# daughter_board.net
KiCad netlist of a schematic drawn in EAGLE
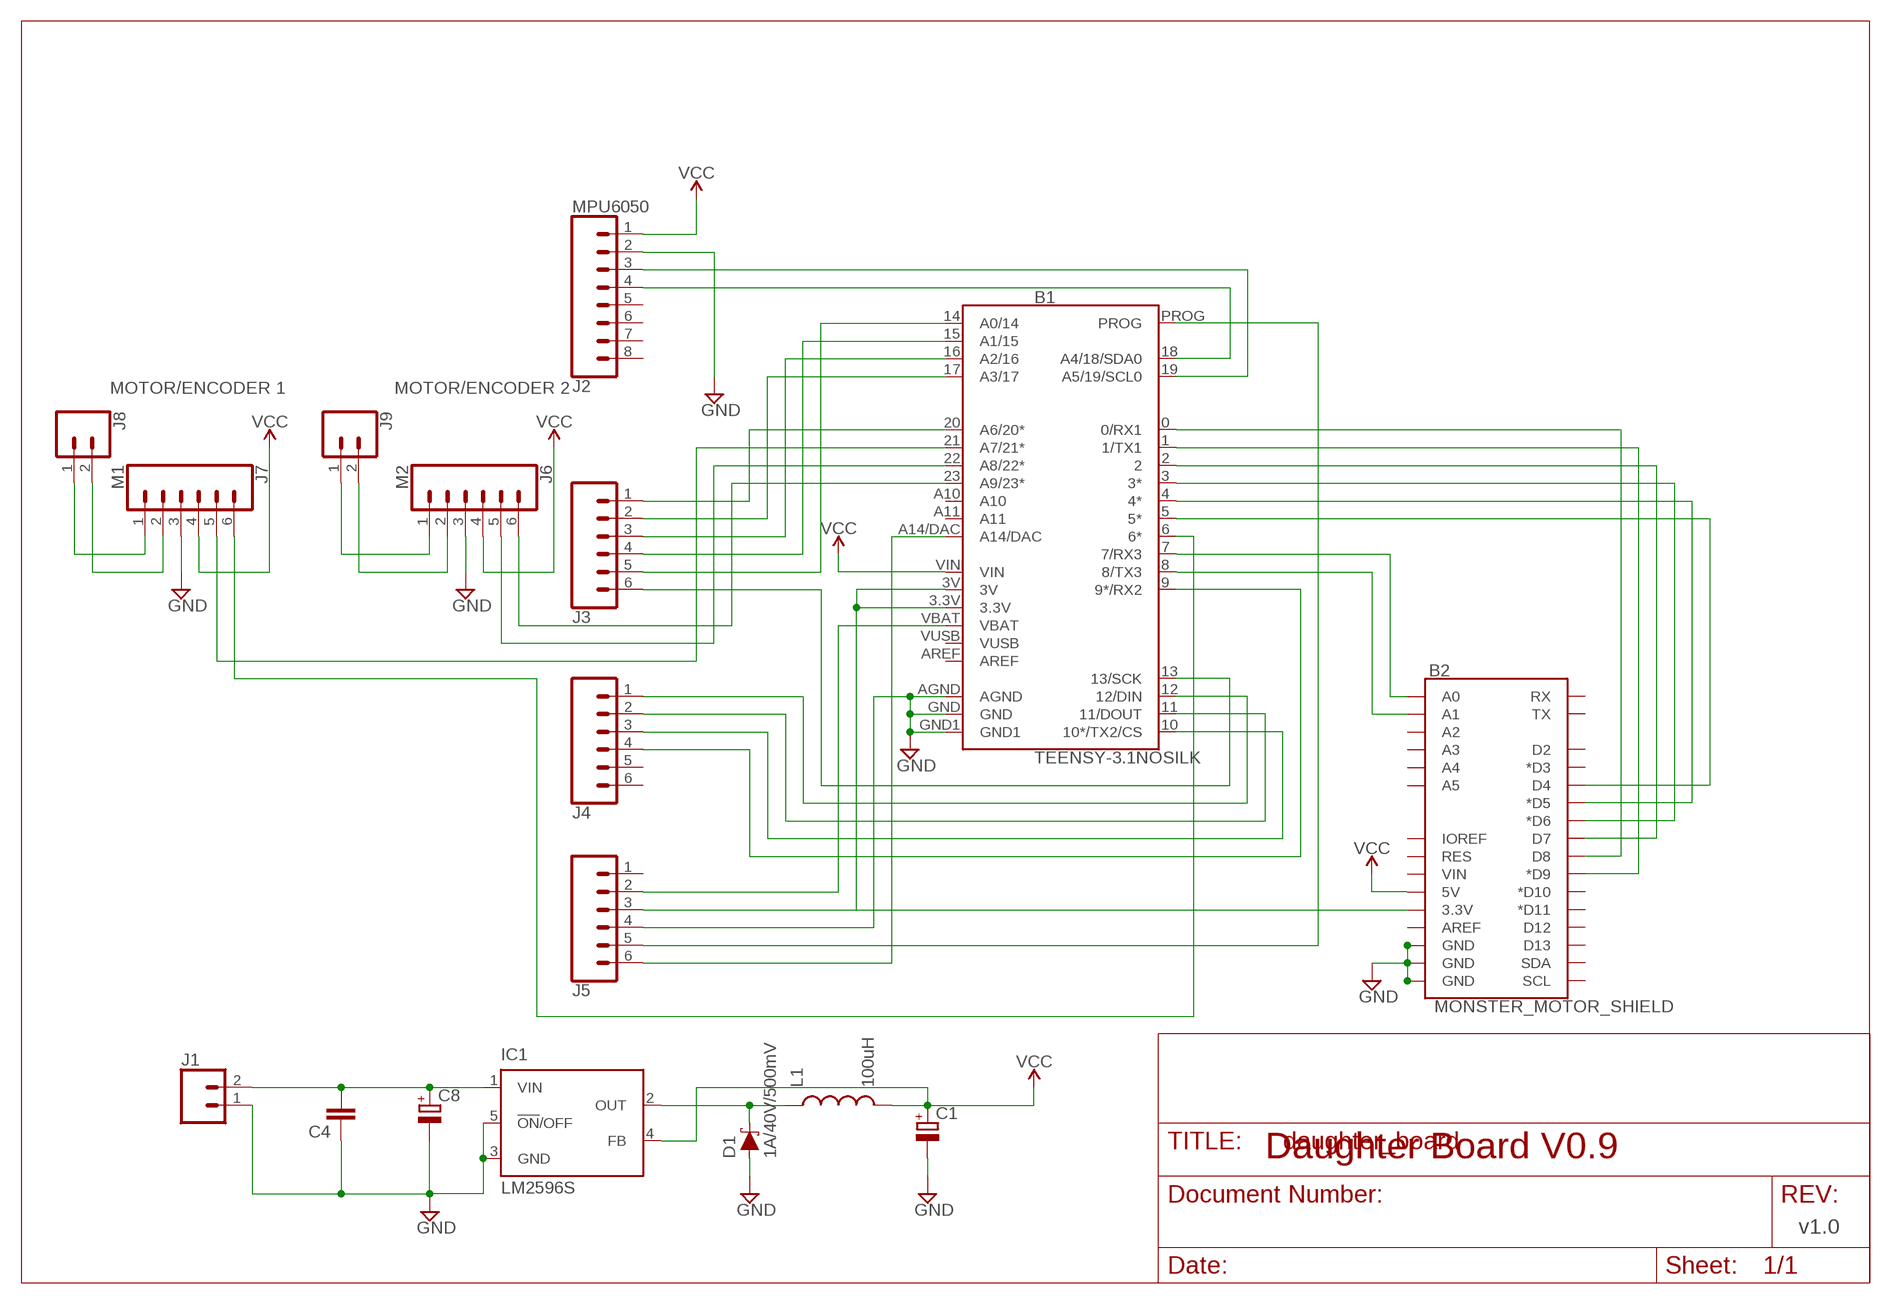
[diagram p0: schematic, sheet 1]

(export (version "E")
  (design (tool "Eeschema 10.0.6"))
  (components
    (comp (ref "B1")
      (value "TEENSY-3.1NOSILK")
      (footprint "eagle-import:TEENSY-3.1_NOSILK")
      (libsource (lib "eagle-import") (part "TEENSY-3.1NOSILK"))
    )
    (comp (ref "B2")
      (value "MONSTER_MOTOR_SHIELD")
      (footprint "eagle-import:UNO_R3_SHIELD_NOLABELS")
      (libsource (lib "eagle-import") (part "ARDUINO_UNO_R3_SHIELDNOLABELS"))
    )
    (comp (ref "C1")
      (value "CPOL-EU150CLZ-0810")
      (footprint "eagle-import:150CLZ-0810")
      (libsource (lib "eagle-import") (part "CPOL-EU150CLZ-0810"))
    )
    (comp (ref "C4")
      (value "C-EUC0805")
      (footprint "eagle-import:C0805")
      (libsource (lib "eagle-import") (part "C-EUC0805"))
    )
    (comp (ref "C8")
      (value "CPOL-EU150CLZ-0810")
      (footprint "eagle-import:150CLZ-0810")
      (libsource (lib "eagle-import") (part "CPOL-EU150CLZ-0810"))
    )
    (comp (ref "D1")
      (value "1A/40V/500mV")
      (footprint "eagle-import:SMA-DIODE")
      (libsource (lib "eagle-import") (part "DIODE-SCHOTTKY-SS14"))
    )
    (comp (ref "IC1")
      (value "LM2596S")
      (footprint "eagle-import:TO263-5")
      (fields (field (name "MF") "NATIONAL SEMICONDUCTOR") (field (name "MPN") "LM2596S-ADJ/NOPB"))
      (libsource (lib "eagle-import") (part "LM2596S"))
    )
    (comp (ref "J1")
      (value "CONN_023.5MM-NO_SILK")
      (footprint "eagle-import:SCREWTERMINAL-3.5MM-2-NS")
      (fields (field (name "PROD_ID") "CONN-08399"))
      (libsource (lib "eagle-import") (part "CONN_023.5MM-NO_SILK"))
    )
    (comp (ref "J2")
      (value "MPU6050")
      (footprint "eagle-import:1X08_NO_SILK")
      (libsource (lib "eagle-import") (part "CONN_08NO_SILK_FEMALE_PTH"))
    )
    (comp (ref "J3")
      (value "CONN_06NO_SILK_FEMALE_PTH")
      (footprint "eagle-import:1X06_NO_SILK")
      (libsource (lib "eagle-import") (part "CONN_06NO_SILK_FEMALE_PTH"))
    )
    (comp (ref "J4")
      (value "CONN_06NO_SILK_FEMALE_PTH")
      (footprint "eagle-import:1X06_NO_SILK")
      (libsource (lib "eagle-import") (part "CONN_06NO_SILK_FEMALE_PTH"))
    )
    (comp (ref "J5")
      (value "CONN_06NO_SILK_FEMALE_PTH")
      (footprint "eagle-import:1X06_NO_SILK")
      (libsource (lib "eagle-import") (part "CONN_06NO_SILK_FEMALE_PTH"))
    )
    (comp (ref "J6")
      (value "M2")
      (footprint "eagle-import:1X06_NO_SILK")
      (libsource (lib "eagle-import") (part "CONN_06NO_SILK_FEMALE_PTH"))
    )
    (comp (ref "J7")
      (value "M1")
      (footprint "eagle-import:1X06_NO_SILK")
      (libsource (lib "eagle-import") (part "CONN_06NO_SILK_FEMALE_PTH"))
    )
    (comp (ref "J8")
      (value "CONN_023.5MM-NO_SILK")
      (footprint "eagle-import:SCREWTERMINAL-3.5MM-2-NS")
      (libsource (lib "eagle-import") (part "CONN_023.5MM-NO_SILK"))
    )
    (comp (ref "J9")
      (value "CONN_023.5MM-NO_SILK")
      (footprint "eagle-import:SCREWTERMINAL-3.5MM-2-NS")
      (libsource (lib "eagle-import") (part "CONN_023.5MM-NO_SILK"))
    )
    (comp (ref "L1")
      (value "100uH")
      (footprint "eagle-import:CDRH125")
      (libsource (lib "eagle-import") (part "INDUCTORPWR"))
    )
  )
  (nets
    (net (code "1") (name "/VUSB") (class "Default")
      (node (ref "B1") (pin "VUSB") (pinfunction "VUSB_VUSB") (pintype "power_in"))
    )
    (net (code "2") (name "GND") (class "Default")
      (node (ref "B1") (pin "AGND") (pinfunction "AGND_AGND") (pintype "power_in"))
      (node (ref "B1") (pin "GND") (pinfunction "GND_GND") (pintype "power_in"))
      (node (ref "B1") (pin "GND1") (pinfunction "GND1_GND1") (pintype "power_in"))
      (node (ref "B2") (pin "GND@0") (pinfunction "GND_GND@0") (pintype "bidirectional"))
      (node (ref "B2") (pin "GND@1") (pinfunction "GND_GND@1") (pintype "bidirectional"))
      (node (ref "B2") (pin "GND@2") (pinfunction "GND_GND@2") (pintype "bidirectional"))
      (node (ref "C1") (pin "-") (pinfunction "-_-") (pintype "passive"))
      (node (ref "C4") (pin "1") (pinfunction "1_1") (pintype "passive"))
      (node (ref "C8") (pin "-") (pinfunction "-_-") (pintype "passive"))
      (node (ref "D1") (pin "A") (pinfunction "A_A") (pintype "passive"))
      (node (ref "IC1") (pin "3") (pinfunction "GND_3") (pintype "power_in"))
      (node (ref "IC1") (pin "5") (pinfunction "~{ON}/OFF_5") (pintype "input"))
      (node (ref "J1") (pin "1") (pinfunction "1_1") (pintype "passive"))
      (node (ref "J2") (pin "2") (pinfunction "2_2") (pintype "passive"))
      (node (ref "J5") (pin "4") (pinfunction "4_4") (pintype "passive"))
      (node (ref "J6") (pin "3") (pinfunction "3_3") (pintype "passive"))
      (node (ref "J7") (pin "3") (pinfunction "3_3") (pintype "passive"))
    )
    (net (code "3") (name "Net-(B1-0{slash}RX1)") (class "Default")
      (node (ref "B1") (pin "0") (pinfunction "0/RX1_0") (pintype "bidirectional"))
      (node (ref "B2") (pin "D8") (pinfunction "D8_D8") (pintype "bidirectional"))
    )
    (net (code "4") (name "Net-(B1-1{slash}TX1)") (class "Default")
      (node (ref "B1") (pin "1") (pinfunction "1/TX1_1") (pintype "bidirectional"))
      (node (ref "B2") (pin "D9") (pinfunction "*D9_D9") (pintype "bidirectional"))
    )
    (net (code "5") (name "Net-(B1-3*)") (class "Default")
      (node (ref "B1") (pin "3") (pinfunction "3*_3") (pintype "bidirectional"))
      (node (ref "B2") (pin "D6") (pinfunction "*D6_D6") (pintype "bidirectional"))
    )
    (net (code "6") (name "Net-(B1-4*)") (class "Default")
      (node (ref "B1") (pin "4") (pinfunction "4*_4") (pintype "bidirectional"))
      (node (ref "B2") (pin "D5") (pinfunction "*D5_D5") (pintype "bidirectional"))
    )
    (net (code "7") (name "Net-(B1-5*)") (class "Default")
      (node (ref "B1") (pin "5") (pinfunction "5*_5") (pintype "bidirectional"))
      (node (ref "B2") (pin "D4") (pinfunction "D4_D4") (pintype "bidirectional"))
    )
    (net (code "8") (name "Net-(B1-6*)") (class "Default")
      (node (ref "B1") (pin "6") (pinfunction "6*_6") (pintype "bidirectional"))
      (node (ref "J7") (pin "6") (pinfunction "6_6") (pintype "passive"))
    )
    (net (code "9") (name "Net-(B1-7{slash}RX3)") (class "Default")
      (node (ref "B1") (pin "7") (pinfunction "7/RX3_7") (pintype "bidirectional"))
      (node (ref "B2") (pin "A0") (pinfunction "A0_A0") (pintype "bidirectional"))
    )
    (net (code "10") (name "Net-(B1-8{slash}TX3)") (class "Default")
      (node (ref "B1") (pin "8") (pinfunction "8/TX3_8") (pintype "bidirectional"))
      (node (ref "B2") (pin "A1") (pinfunction "A1_A1") (pintype "bidirectional"))
    )
    (net (code "11") (name "Net-(B1-9*{slash}RX2)") (class "Default")
      (node (ref "B1") (pin "9") (pinfunction "9*/RX2_9") (pintype "bidirectional"))
      (node (ref "J4") (pin "4") (pinfunction "4_4") (pintype "passive"))
    )
    (net (code "12") (name "Net-(B1-10*{slash}TX2{slash}CS)") (class "Default")
      (node (ref "B1") (pin "10") (pinfunction "10*/TX2/CS_10") (pintype "bidirectional"))
      (node (ref "J4") (pin "3") (pinfunction "3_3") (pintype "passive"))
    )
    (net (code "13") (name "Net-(B1-11{slash}DOUT)") (class "Default")
      (node (ref "B1") (pin "11") (pinfunction "11/DOUT_11") (pintype "bidirectional"))
      (node (ref "J4") (pin "2") (pinfunction "2_2") (pintype "passive"))
    )
    (net (code "14") (name "Net-(B1-12{slash}DIN)") (class "Default")
      (node (ref "B1") (pin "12") (pinfunction "12/DIN_12") (pintype "bidirectional"))
      (node (ref "J4") (pin "1") (pinfunction "1_1") (pintype "passive"))
    )
    (net (code "15") (name "Net-(B1-13{slash}SCK)") (class "Default")
      (node (ref "B1") (pin "13") (pinfunction "13/SCK_13") (pintype "bidirectional"))
      (node (ref "J3") (pin "6") (pinfunction "6_6") (pintype "passive"))
    )
    (net (code "16") (name "Net-(B1-A0{slash}14)") (class "Default")
      (node (ref "B1") (pin "14") (pinfunction "A0/14_14") (pintype "bidirectional"))
      (node (ref "J3") (pin "5") (pinfunction "5_5") (pintype "passive"))
    )
    (net (code "17") (name "Net-(B1-A1{slash}15)") (class "Default")
      (node (ref "B1") (pin "15") (pinfunction "A1/15_15") (pintype "bidirectional"))
      (node (ref "J3") (pin "4") (pinfunction "4_4") (pintype "passive"))
    )
    (net (code "18") (name "Net-(B1-A2{slash}16)") (class "Default")
      (node (ref "B1") (pin "16") (pinfunction "A2/16_16") (pintype "bidirectional"))
      (node (ref "J3") (pin "3") (pinfunction "3_3") (pintype "passive"))
    )
    (net (code "19") (name "Net-(B1-A3{slash}17)") (class "Default")
      (node (ref "B1") (pin "17") (pinfunction "A3/17_17") (pintype "bidirectional"))
      (node (ref "J3") (pin "2") (pinfunction "2_2") (pintype "passive"))
    )
    (net (code "20") (name "Net-(B1-A4{slash}18{slash}SDA0)") (class "Default")
      (node (ref "B1") (pin "18") (pinfunction "A4/18/SDA0_18") (pintype "bidirectional"))
      (node (ref "J2") (pin "4") (pinfunction "4_4") (pintype "passive"))
    )
    (net (code "21") (name "Net-(B1-A5{slash}19{slash}SCL0)") (class "Default")
      (node (ref "B1") (pin "19") (pinfunction "A5/19/SCL0_19") (pintype "bidirectional"))
      (node (ref "J2") (pin "3") (pinfunction "3_3") (pintype "passive"))
    )
    (net (code "22") (name "Net-(B1-A6{slash}20*)") (class "Default")
      (node (ref "B1") (pin "20") (pinfunction "A6/20*_20") (pintype "bidirectional"))
      (node (ref "J3") (pin "1") (pinfunction "1_1") (pintype "passive"))
    )
    (net (code "23") (name "Net-(B1-A7{slash}21*)") (class "Default")
      (node (ref "B1") (pin "21") (pinfunction "A7/21*_21") (pintype "bidirectional"))
      (node (ref "J7") (pin "5") (pinfunction "5_5") (pintype "passive"))
    )
    (net (code "24") (name "Net-(B1-A8{slash}22*)") (class "Default")
      (node (ref "B1") (pin "22") (pinfunction "A8/22*_22") (pintype "bidirectional"))
      (node (ref "J6") (pin "5") (pinfunction "5_5") (pintype "passive"))
    )
    (net (code "25") (name "Net-(B1-A9{slash}23*)") (class "Default")
      (node (ref "B1") (pin "23") (pinfunction "A9/23*_23") (pintype "bidirectional"))
      (node (ref "J6") (pin "6") (pinfunction "6_6") (pintype "passive"))
    )
    (net (code "26") (name "Net-(B1-Pad2)") (class "Default")
      (node (ref "B1") (pin "2") (pinfunction "2_2") (pintype "bidirectional"))
      (node (ref "B2") (pin "D7") (pinfunction "D7_D7") (pintype "bidirectional"))
    )
    (net (code "27") (name "Net-(B1-Pad3.3V)") (class "Default")
      (node (ref "B1") (pin "3.3V") (pinfunction "3.3V_3.3V") (pintype "power_in"))
      (node (ref "B1") (pin "3V") (pinfunction "3V_3V") (pintype "power_in"))
      (node (ref "B2") (pin "3.3V") (pinfunction "3.3V_3.3V") (pintype "bidirectional"))
      (node (ref "J5") (pin "3") (pinfunction "3_3") (pintype "passive"))
    )
    (net (code "28") (name "Net-(B1-PadA14{slash}DAC)") (class "Default")
      (node (ref "B1") (pin "A14/DAC") (pinfunction "A14/DAC_A14/DAC") (pintype "bidirectional"))
      (node (ref "J5") (pin "6") (pinfunction "6_6") (pintype "passive"))
    )
    (net (code "29") (name "Net-(B1-PadPROG)") (class "Default")
      (node (ref "B1") (pin "PROG") (pinfunction "PROG_PROG") (pintype "bidirectional"))
      (node (ref "J5") (pin "5") (pinfunction "5_5") (pintype "passive"))
    )
    (net (code "30") (name "Net-(B1-PadVBAT)") (class "Default")
      (node (ref "B1") (pin "VBAT") (pinfunction "VBAT_VBAT") (pintype "power_in"))
      (node (ref "J5") (pin "2") (pinfunction "2_2") (pintype "passive"))
    )
    (net (code "31") (name "Net-(IC1-OUT)") (class "Default")
      (node (ref "D1") (pin "C") (pinfunction "C_C") (pintype "passive"))
      (node (ref "IC1") (pin "2") (pinfunction "OUT_2") (pintype "output"))
      (node (ref "L1") (pin "1") (pinfunction "1_1") (pintype "passive"))
    )
    (net (code "32") (name "Net-(IC1-VIN)") (class "Default")
      (node (ref "C4") (pin "2") (pinfunction "2_2") (pintype "passive"))
      (node (ref "C8") (pin "+") (pinfunction "+_+") (pintype "passive"))
      (node (ref "IC1") (pin "1") (pinfunction "VIN_1") (pintype "input"))
      (node (ref "J1") (pin "2") (pinfunction "2_2") (pintype "passive"))
    )
    (net (code "33") (name "Net-(J6-Pad1)") (class "Default")
      (node (ref "J6") (pin "1") (pinfunction "1_1") (pintype "passive"))
      (node (ref "J9") (pin "1") (pinfunction "1_1") (pintype "passive"))
    )
    (net (code "34") (name "Net-(J6-Pad2)") (class "Default")
      (node (ref "J6") (pin "2") (pinfunction "2_2") (pintype "passive"))
      (node (ref "J9") (pin "2") (pinfunction "2_2") (pintype "passive"))
    )
    (net (code "35") (name "Net-(J7-Pad1)") (class "Default")
      (node (ref "J7") (pin "1") (pinfunction "1_1") (pintype "passive"))
      (node (ref "J8") (pin "1") (pinfunction "1_1") (pintype "passive"))
    )
    (net (code "36") (name "Net-(J7-Pad2)") (class "Default")
      (node (ref "J7") (pin "2") (pinfunction "2_2") (pintype "passive"))
      (node (ref "J8") (pin "2") (pinfunction "2_2") (pintype "passive"))
    )
    (net (code "37") (name "VCC") (class "Default")
      (node (ref "B1") (pin "VIN") (pinfunction "VIN_VIN") (pintype "power_in"))
      (node (ref "B2") (pin "5V") (pinfunction "5V_5V") (pintype "bidirectional"))
      (node (ref "C1") (pin "+") (pinfunction "+_+") (pintype "passive"))
      (node (ref "IC1") (pin "4") (pinfunction "FB_4") (pintype "input"))
      (node (ref "J2") (pin "1") (pinfunction "1_1") (pintype "passive"))
      (node (ref "J6") (pin "4") (pinfunction "4_4") (pintype "passive"))
      (node (ref "J7") (pin "4") (pinfunction "4_4") (pintype "passive"))
      (node (ref "L1") (pin "2") (pinfunction "2_2") (pintype "passive"))
    )
    (net (code "38") (name "unconnected-(B1-PadA10)") (class "Default")
      (node (ref "B1") (pin "A10") (pinfunction "A10_A10") (pintype "bidirectional"))
    )
    (net (code "39") (name "unconnected-(B1-PadA11)") (class "Default")
      (node (ref "B1") (pin "A11") (pinfunction "A11_A11") (pintype "bidirectional"))
    )
    (net (code "40") (name "unconnected-(B1-PadAREF)") (class "Default")
      (node (ref "B1") (pin "AREF") (pinfunction "AREF_AREF") (pintype "bidirectional"))
    )
    (net (code "41") (name "unconnected-(B2-*D3-PadD3)") (class "Default")
      (node (ref "B2") (pin "D3") (pinfunction "*D3_D3") (pintype "bidirectional"))
    )
    (net (code "42") (name "unconnected-(B2-*D10-PadD10)") (class "Default")
      (node (ref "B2") (pin "D10") (pinfunction "*D10_D10") (pintype "bidirectional"))
    )
    (net (code "43") (name "unconnected-(B2-*D11-PadD11)") (class "Default")
      (node (ref "B2") (pin "D11") (pinfunction "*D11_D11") (pintype "bidirectional"))
    )
    (net (code "44") (name "unconnected-(B2-PadA2)") (class "Default")
      (node (ref "B2") (pin "A2") (pinfunction "A2_A2") (pintype "bidirectional"))
    )
    (net (code "45") (name "unconnected-(B2-PadA3)") (class "Default")
      (node (ref "B2") (pin "A3") (pinfunction "A3_A3") (pintype "bidirectional"))
    )
    (net (code "46") (name "unconnected-(B2-PadA4)") (class "Default")
      (node (ref "B2") (pin "A4") (pinfunction "A4_A4") (pintype "bidirectional"))
    )
    (net (code "47") (name "unconnected-(B2-PadA5)") (class "Default")
      (node (ref "B2") (pin "A5") (pinfunction "A5_A5") (pintype "bidirectional"))
    )
    (net (code "48") (name "unconnected-(B2-PadAREF)") (class "Default")
      (node (ref "B2") (pin "AREF") (pinfunction "AREF_AREF") (pintype "bidirectional"))
    )
    (net (code "49") (name "unconnected-(B2-PadD2)") (class "Default")
      (node (ref "B2") (pin "D2") (pinfunction "D2_D2") (pintype "bidirectional"))
    )
    (net (code "50") (name "unconnected-(B2-PadD12)") (class "Default")
      (node (ref "B2") (pin "D12") (pinfunction "D12_D12") (pintype "bidirectional"))
    )
    (net (code "51") (name "unconnected-(B2-PadD13)") (class "Default")
      (node (ref "B2") (pin "D13") (pinfunction "D13_D13") (pintype "bidirectional"))
    )
    (net (code "52") (name "unconnected-(B2-PadIOREF)") (class "Default")
      (node (ref "B2") (pin "IOREF") (pinfunction "IOREF_IOREF") (pintype "bidirectional"))
    )
    (net (code "53") (name "unconnected-(B2-PadRES)") (class "Default")
      (node (ref "B2") (pin "RES") (pinfunction "RES_RES") (pintype "bidirectional"))
    )
    (net (code "54") (name "unconnected-(B2-PadRX)") (class "Default")
      (node (ref "B2") (pin "RX") (pinfunction "RX_RX") (pintype "bidirectional"))
    )
    (net (code "55") (name "unconnected-(B2-PadSCL)") (class "Default")
      (node (ref "B2") (pin "SCL") (pinfunction "SCL_SCL") (pintype "bidirectional"))
    )
    (net (code "56") (name "unconnected-(B2-PadSDA)") (class "Default")
      (node (ref "B2") (pin "SDA") (pinfunction "SDA_SDA") (pintype "bidirectional"))
    )
    (net (code "57") (name "unconnected-(B2-PadTX)") (class "Default")
      (node (ref "B2") (pin "TX") (pinfunction "TX_TX") (pintype "bidirectional"))
    )
    (net (code "58") (name "unconnected-(B2-PadVIN)") (class "Default")
      (node (ref "B2") (pin "VIN") (pinfunction "VIN_VIN") (pintype "bidirectional"))
    )
    (net (code "59") (name "unconnected-(J2-Pad5)") (class "Default")
      (node (ref "J2") (pin "5") (pinfunction "5_5") (pintype "passive"))
    )
    (net (code "60") (name "unconnected-(J2-Pad6)") (class "Default")
      (node (ref "J2") (pin "6") (pinfunction "6_6") (pintype "passive"))
    )
    (net (code "61") (name "unconnected-(J2-Pad7)") (class "Default")
      (node (ref "J2") (pin "7") (pinfunction "7_7") (pintype "passive"))
    )
    (net (code "62") (name "unconnected-(J2-Pad8)") (class "Default")
      (node (ref "J2") (pin "8") (pinfunction "8_8") (pintype "passive"))
    )
    (net (code "63") (name "unconnected-(J4-Pad5)") (class "Default")
      (node (ref "J4") (pin "5") (pinfunction "5_5") (pintype "passive"))
    )
    (net (code "64") (name "unconnected-(J4-Pad6)") (class "Default")
      (node (ref "J4") (pin "6") (pinfunction "6_6") (pintype "passive"))
    )
    (net (code "65") (name "unconnected-(J5-Pad1)") (class "Default")
      (node (ref "J5") (pin "1") (pinfunction "1_1") (pintype "passive"))
    )
  )
)
